# JAjchel_schemat.net
KiCad netlist of a schematic drawn in Altium Designer
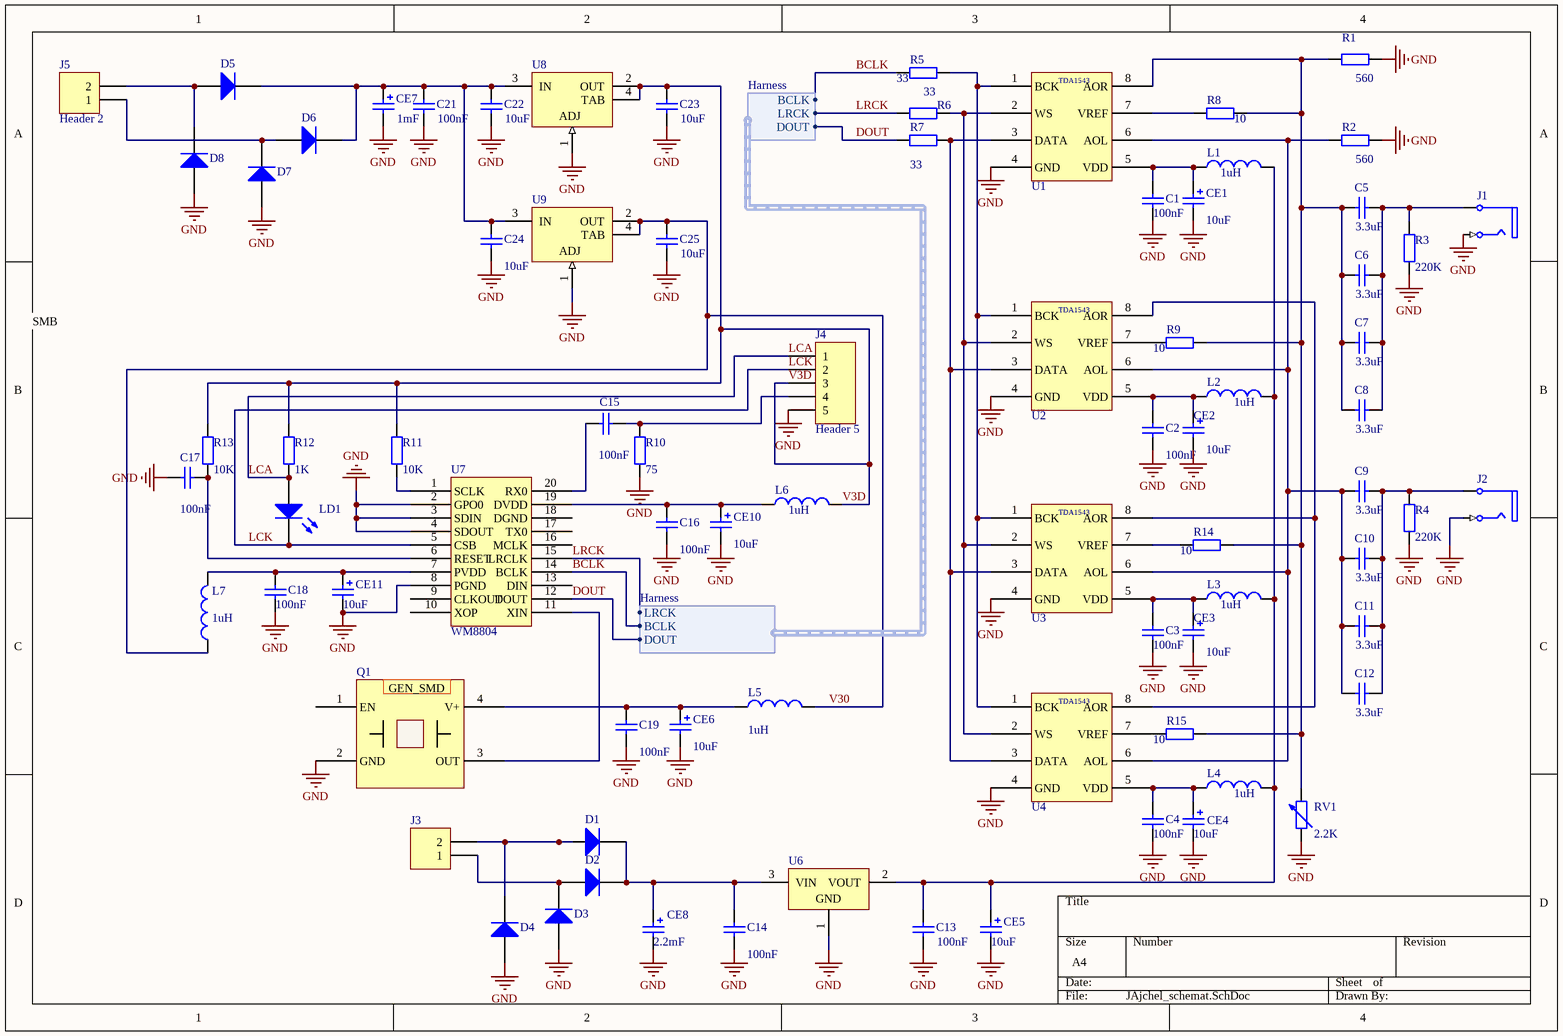
[diagram p0: JAjchel_schemat.SchDoc]

(export (version "E")
  (design (tool "Eeschema 10.0.6"))
  (components
    (comp (ref "C1")
      (value "100nF")
      (footprint "RAD-0.3")
      (description "Capacitor")
      (fields (field (name "Comment") "Cap") (field (name "PUBLISHER") "Altium Limited"))
      (libsource (lib "Miscellaneous Devices") (part "Cap"))
    )
    (comp (ref "C2")
      (value "100nF")
      (footprint "RAD-0.3")
      (description "Capacitor")
      (fields (field (name "Comment") "Cap") (field (name "PUBLISHER") "Altium Limited"))
      (libsource (lib "Miscellaneous Devices") (part "Cap"))
    )
    (comp (ref "C3")
      (value "100nF")
      (footprint "RAD-0.3")
      (description "Capacitor")
      (fields (field (name "Comment") "Cap") (field (name "PUBLISHER") "Altium Limited"))
      (libsource (lib "Miscellaneous Devices") (part "Cap"))
    )
    (comp (ref "C4")
      (value "100nF")
      (footprint "RAD-0.3")
      (description "Capacitor")
      (fields (field (name "Comment") "Cap") (field (name "PUBLISHER") "Altium Limited"))
      (libsource (lib "Miscellaneous Devices") (part "Cap"))
    )
    (comp (ref "C5")
      (value "3.3uF")
      (footprint "RAD-0.3")
      (description "Capacitor")
      (fields (field (name "Comment") "Cap") (field (name "PUBLISHER") "Altium Limited"))
      (libsource (lib "Miscellaneous Devices") (part "Cap"))
    )
    (comp (ref "C6")
      (value "3.3uF")
      (footprint "RAD-0.3")
      (description "Capacitor")
      (fields (field (name "Comment") "Cap") (field (name "PUBLISHER") "Altium Limited"))
      (libsource (lib "Miscellaneous Devices") (part "Cap"))
    )
    (comp (ref "C7")
      (value "3.3uF")
      (footprint "RAD-0.3")
      (description "Capacitor")
      (fields (field (name "Comment") "Cap") (field (name "PUBLISHER") "Altium Limited"))
      (libsource (lib "Miscellaneous Devices") (part "Cap"))
    )
    (comp (ref "C8")
      (value "3.3uF")
      (footprint "RAD-0.3")
      (description "Capacitor")
      (fields (field (name "Comment") "Cap") (field (name "PUBLISHER") "Altium Limited"))
      (libsource (lib "Miscellaneous Devices") (part "Cap"))
    )
    (comp (ref "C9")
      (value "3.3uF")
      (footprint "RAD-0.3")
      (description "Capacitor")
      (fields (field (name "Comment") "Cap") (field (name "PUBLISHER") "Altium Limited"))
      (libsource (lib "Miscellaneous Devices") (part "Cap"))
    )
    (comp (ref "C10")
      (value "3.3uF")
      (footprint "RAD-0.3")
      (description "Capacitor")
      (fields (field (name "Comment") "Cap") (field (name "PUBLISHER") "Altium Limited"))
      (libsource (lib "Miscellaneous Devices") (part "Cap"))
    )
    (comp (ref "C11")
      (value "3.3uF")
      (footprint "RAD-0.3")
      (description "Capacitor")
      (fields (field (name "Comment") "Cap") (field (name "PUBLISHER") "Altium Limited"))
      (libsource (lib "Miscellaneous Devices") (part "Cap"))
    )
    (comp (ref "C12")
      (value "3.3uF")
      (footprint "RAD-0.3")
      (description "Capacitor")
      (fields (field (name "Comment") "Cap") (field (name "PUBLISHER") "Altium Limited"))
      (libsource (lib "Miscellaneous Devices") (part "Cap"))
    )
    (comp (ref "C13")
      (value "100nF")
      (footprint "RAD-0.3")
      (description "Capacitor")
      (fields (field (name "Comment") "Cap") (field (name "PUBLISHER") "Altium Limited"))
      (libsource (lib "Miscellaneous Devices") (part "Cap"))
    )
    (comp (ref "C14")
      (value "100nF")
      (footprint "RAD-0.3")
      (description "Capacitor")
      (fields (field (name "Comment") "Cap") (field (name "PUBLISHER") "Altium Limited"))
      (libsource (lib "Miscellaneous Devices") (part "Cap"))
    )
    (comp (ref "C15")
      (value "100nF")
      (footprint "RAD-0.3")
      (description "Capacitor")
      (fields (field (name "Comment") "Cap") (field (name "PUBLISHER") "Altium Limited"))
      (libsource (lib "Miscellaneous Devices") (part "Cap"))
    )
    (comp (ref "C16")
      (value "100nF")
      (footprint "RAD-0.3")
      (description "Capacitor")
      (fields (field (name "Comment") "Cap") (field (name "PUBLISHER") "Altium Limited"))
      (libsource (lib "Miscellaneous Devices") (part "Cap"))
    )
    (comp (ref "C17")
      (value "100nF")
      (footprint "RAD-0.3")
      (description "Capacitor")
      (fields (field (name "Comment") "Cap") (field (name "PUBLISHER") "Altium Limited"))
      (libsource (lib "Miscellaneous Devices") (part "Cap"))
    )
    (comp (ref "C18")
      (value "100nF")
      (footprint "RAD-0.3")
      (description "Capacitor")
      (fields (field (name "Comment") "Cap") (field (name "PUBLISHER") "Altium Limited"))
      (libsource (lib "Miscellaneous Devices") (part "Cap"))
    )
    (comp (ref "C19")
      (value "100nF")
      (footprint "RAD-0.3")
      (description "Capacitor")
      (fields (field (name "Comment") "Cap") (field (name "PUBLISHER") "Altium Limited"))
      (libsource (lib "Miscellaneous Devices") (part "Cap"))
    )
    (comp (ref "C21")
      (value "100nF")
      (footprint "RAD-0.3")
      (description "Capacitor")
      (fields (field (name "Comment") "Cap") (field (name "PUBLISHER") "Altium Limited"))
      (libsource (lib "Miscellaneous Devices") (part "Cap"))
    )
    (comp (ref "C22")
      (value "10uF")
      (footprint "RAD-0.3")
      (description "Capacitor")
      (fields (field (name "Comment") "Cap") (field (name "PUBLISHER") "Altium Limited"))
      (libsource (lib "Miscellaneous Devices") (part "Cap"))
    )
    (comp (ref "C23")
      (value "10uF")
      (footprint "RAD-0.3")
      (description "Capacitor")
      (fields (field (name "Comment") "Cap") (field (name "PUBLISHER") "Altium Limited"))
      (libsource (lib "Miscellaneous Devices") (part "Cap"))
    )
    (comp (ref "C24")
      (value "10uF")
      (footprint "RAD-0.3")
      (description "Capacitor")
      (fields (field (name "Comment") "Cap") (field (name "PUBLISHER") "Altium Limited"))
      (libsource (lib "Miscellaneous Devices") (part "Cap"))
    )
    (comp (ref "C25")
      (value "10uF")
      (footprint "RAD-0.3")
      (description "Capacitor")
      (fields (field (name "Comment") "Cap") (field (name "PUBLISHER") "Altium Limited"))
      (libsource (lib "Miscellaneous Devices") (part "Cap"))
    )
    (comp (ref "CE1")
      (value "10uF")
      (footprint "POLAR0.8")
      (description "Polarized Capacitor (Axial)")
      (fields (field (name "Comment") "Cap Pol2") (field (name "PUBLISHER") "Altium Limited"))
      (libsource (lib "Miscellaneous Devices") (part "Cap Pol2"))
    )
    (comp (ref "CE2")
      (value "10uF")
      (footprint "POLAR0.8")
      (description "Polarized Capacitor (Axial)")
      (fields (field (name "Comment") "Cap Pol2") (field (name "PUBLISHER") "Altium Limited"))
      (libsource (lib "Miscellaneous Devices") (part "Cap Pol2"))
    )
    (comp (ref "CE3")
      (value "10uF")
      (footprint "POLAR0.8")
      (description "Polarized Capacitor (Axial)")
      (fields (field (name "Comment") "Cap Pol2") (field (name "PUBLISHER") "Altium Limited"))
      (libsource (lib "Miscellaneous Devices") (part "Cap Pol2"))
    )
    (comp (ref "CE4")
      (value "10uF")
      (footprint "POLAR0.8")
      (description "Polarized Capacitor (Axial)")
      (fields (field (name "Comment") "Cap Pol2") (field (name "PUBLISHER") "Altium Limited"))
      (libsource (lib "Miscellaneous Devices") (part "Cap Pol2"))
    )
    (comp (ref "CE5")
      (value "10uF")
      (footprint "POLAR0.8")
      (description "Polarized Capacitor (Axial)")
      (fields (field (name "Comment") "Cap Pol2") (field (name "PUBLISHER") "Altium Limited"))
      (libsource (lib "Miscellaneous Devices") (part "Cap Pol2"))
    )
    (comp (ref "CE6")
      (value "10uF")
      (footprint "POLAR0.8")
      (description "Polarized Capacitor (Axial)")
      (fields (field (name "Comment") "Cap Pol2") (field (name "PUBLISHER") "Altium Limited"))
      (libsource (lib "Miscellaneous Devices") (part "Cap Pol2"))
    )
    (comp (ref "CE7")
      (value "1mF")
      (footprint "POLAR0.8")
      (description "Polarized Capacitor (Axial)")
      (fields (field (name "Comment") "Cap Pol2") (field (name "PUBLISHER") "Altium Limited"))
      (libsource (lib "Miscellaneous Devices") (part "Cap Pol2"))
    )
    (comp (ref "CE8")
      (value "2.2mF")
      (footprint "POLAR0.8")
      (description "Polarized Capacitor (Axial)")
      (fields (field (name "Comment") "Cap Pol2") (field (name "PUBLISHER") "Altium Limited"))
      (libsource (lib "Miscellaneous Devices") (part "Cap Pol2"))
    )
    (comp (ref "CE10")
      (value "10uF")
      (footprint "POLAR0.8")
      (description "Polarized Capacitor (Axial)")
      (fields (field (name "Comment") "Cap Pol2") (field (name "PUBLISHER") "Altium Limited"))
      (libsource (lib "Miscellaneous Devices") (part "Cap Pol2"))
    )
    (comp (ref "CE11")
      (value "10uF")
      (footprint "POLAR0.8")
      (description "Polarized Capacitor (Axial)")
      (fields (field (name "Comment") "Cap Pol2") (field (name "PUBLISHER") "Altium Limited"))
      (libsource (lib "Miscellaneous Devices") (part "Cap Pol2"))
    )
    (comp (ref "D1") (value "D-AK-2") (libsource (lib "D-AK-2") (part "D-AK-2")))
    (comp (ref "D2") (value "D-AK-2") (libsource (lib "D-AK-2") (part "D-AK-2")))
    (comp (ref "D3") (value "D-AK-2") (libsource (lib "D-AK-2") (part "D-AK-2")))
    (comp (ref "D4") (value "D-AK-2") (libsource (lib "Altium Content Vault") (part "SYM-0080-00036-1")))
    (comp (ref "D5") (value "D-AK-2") (libsource (lib "D-AK-2") (part "D-AK-2")))
    (comp (ref "D6") (value "D-AK-2") (libsource (lib "D-AK-2") (part "D-AK-2")))
    (comp (ref "D7") (value "D-AK-2") (libsource (lib "D-AK-2") (part "D-AK-2")))
    (comp (ref "D8") (value "D-AK-2") (libsource (lib "D-AK-2") (part "D-AK-2")))
    (comp (ref "J1")
      (value "RCA")
      (footprint "RCA/4.5-H2")
      (description "RCA Phono Jack, Right Angle, Thru-Hole, Snap-In")
      (fields (field (name "PUBLISHER") "Altium Limited"))
      (libsource (lib "Miscellaneous Connectors") (part "RCA"))
    )
    (comp (ref "J2")
      (value "RCA")
      (footprint "RCA/4.5-H2")
      (description "RCA Phono Jack, Right Angle, Thru-Hole, Snap-In")
      (fields (field (name "PUBLISHER") "Altium Limited"))
      (libsource (lib "Miscellaneous Connectors") (part "RCA"))
    )
    (comp (ref "J3")
      (value "Header 2")
      (footprint "HDR1X2")
      (description "Header, 2-Pin")
      (fields (field (name "PUBLISHER") "Altium Limited"))
      (libsource (lib "Miscellaneous Connectors") (part "Header 2"))
    )
    (comp (ref "J4")
      (value "Header 5")
      (footprint "HDR1X5")
      (description "Header, 5-Pin")
      (fields (field (name "PUBLISHER") "Altium Limited"))
      (libsource (lib "Miscellaneous Connectors") (part "Header 5"))
    )
    (comp (ref "J5")
      (value "Header 2")
      (footprint "HDR1X2")
      (description "Header, 2-Pin")
      (fields (field (name "PUBLISHER") "Altium Limited"))
      (libsource (lib "Miscellaneous Connectors") (part "Header 2"))
    )
    (comp (ref "L1")
      (value "1uH")
      (footprint "0402-A")
      (description "Inductor")
      (fields (field (name "PUBLISHER") "Altium Limited"))
      (libsource (lib "Miscellaneous Devices") (part "Inductor"))
    )
    (comp (ref "L2")
      (value "1uH")
      (footprint "0402-A")
      (description "Inductor")
      (fields (field (name "PUBLISHER") "Altium Limited"))
      (libsource (lib "Miscellaneous Devices") (part "Inductor"))
    )
    (comp (ref "L3")
      (value "1uH")
      (footprint "0402-A")
      (description "Inductor")
      (fields (field (name "PUBLISHER") "Altium Limited"))
      (libsource (lib "Miscellaneous Devices") (part "Inductor"))
    )
    (comp (ref "L4")
      (value "1uH")
      (footprint "0402-A")
      (description "Inductor")
      (fields (field (name "PUBLISHER") "Altium Limited"))
      (libsource (lib "Miscellaneous Devices") (part "Inductor"))
    )
    (comp (ref "L5")
      (value "1uH")
      (footprint "0402-A")
      (description "Inductor")
      (fields (field (name "PUBLISHER") "Altium Limited"))
      (libsource (lib "Miscellaneous Devices") (part "Inductor"))
    )
    (comp (ref "L6")
      (value "1uH")
      (footprint "0402-A")
      (description "Inductor")
      (fields (field (name "PUBLISHER") "Altium Limited"))
      (libsource (lib "Miscellaneous Devices") (part "Inductor"))
    )
    (comp (ref "L7")
      (value "1uH")
      (footprint "0402-A")
      (description "Inductor")
      (fields (field (name "PUBLISHER") "Altium Limited"))
      (libsource (lib "Miscellaneous Devices") (part "Inductor"))
    )
    (comp (ref "LD1")
      (value "LED1")
      (footprint "LED-1")
      (description "Typical RED GaAs LED")
      (fields (field (name "PUBLISHER") "Altium Limited"))
      (libsource (lib "Miscellaneous Devices") (part "LED1"))
    )
    (comp (ref "Q1")
      (value "12MHz")
      (description "Oscilator 12MHz")
      (libsource (lib "JAjchel_projekt") (part "Oscilator12mhz"))
    )
    (comp (ref "R1")
      (value "560")
      (footprint "AXIAL-0.4")
      (description "Resistor")
      (fields (field (name "Comment") "Res2") (field (name "PUBLISHER") "Altium Limited"))
      (libsource (lib "Miscellaneous Devices") (part "Res2"))
    )
    (comp (ref "R2")
      (value "560")
      (footprint "AXIAL-0.4")
      (description "Resistor")
      (fields (field (name "Comment") "Res2") (field (name "PUBLISHER") "Altium Limited"))
      (libsource (lib "Miscellaneous Devices") (part "Res2"))
    )
    (comp (ref "R3")
      (value "220K")
      (footprint "AXIAL-0.4")
      (description "Resistor")
      (fields (field (name "Comment") "Res2") (field (name "PUBLISHER") "Altium Limited"))
      (libsource (lib "") (part "Res2_1"))
    )
    (comp (ref "R4")
      (value "220K")
      (footprint "AXIAL-0.4")
      (description "Resistor")
      (fields (field (name "Comment") "Res2") (field (name "PUBLISHER") "Altium Limited"))
      (libsource (lib "") (part "Res2_1"))
    )
    (comp (ref "R5")
      (value "33")
      (footprint "AXIAL-0.4")
      (description "Resistor")
      (fields (field (name "Comment") "Res2") (field (name "PUBLISHER") "Altium Limited"))
      (libsource (lib "Miscellaneous Devices") (part "Res2"))
    )
    (comp (ref "R6")
      (value "33")
      (footprint "AXIAL-0.4")
      (description "Resistor")
      (fields (field (name "Comment") "Res2") (field (name "PUBLISHER") "Altium Limited"))
      (libsource (lib "Miscellaneous Devices") (part "Res2"))
    )
    (comp (ref "R7")
      (value "33")
      (footprint "AXIAL-0.4")
      (description "Resistor")
      (fields (field (name "Comment") "Res2") (field (name "PUBLISHER") "Altium Limited"))
      (libsource (lib "Miscellaneous Devices") (part "Res2"))
    )
    (comp (ref "R8")
      (value "10")
      (footprint "AXIAL-0.4")
      (description "Resistor")
      (fields (field (name "Comment") "Res2") (field (name "PUBLISHER") "Altium Limited"))
      (libsource (lib "Miscellaneous Devices") (part "Res2"))
    )
    (comp (ref "R9")
      (value "10")
      (footprint "AXIAL-0.4")
      (description "Resistor")
      (fields (field (name "Comment") "Res2") (field (name "PUBLISHER") "Altium Limited"))
      (libsource (lib "Miscellaneous Devices") (part "Res2"))
    )
    (comp (ref "R10")
      (value "75")
      (footprint "AXIAL-0.4")
      (description "Resistor")
      (fields (field (name "Comment") "Res2") (field (name "PUBLISHER") "Altium Limited"))
      (libsource (lib "") (part "Res2_1"))
    )
    (comp (ref "R11")
      (value "10K")
      (footprint "AXIAL-0.4")
      (description "Resistor")
      (fields (field (name "Comment") "Res2") (field (name "PUBLISHER") "Altium Limited"))
      (libsource (lib "") (part "Res2_1"))
    )
    (comp (ref "R12")
      (value "1K")
      (footprint "AXIAL-0.4")
      (description "Resistor")
      (fields (field (name "Comment") "Res2") (field (name "PUBLISHER") "Altium Limited"))
      (libsource (lib "") (part "Res2_1"))
    )
    (comp (ref "R13")
      (value "10K")
      (footprint "AXIAL-0.4")
      (description "Resistor")
      (fields (field (name "Comment") "Res2") (field (name "PUBLISHER") "Altium Limited"))
      (libsource (lib "") (part "Res2_1"))
    )
    (comp (ref "R14")
      (value "10")
      (footprint "AXIAL-0.4")
      (description "Resistor")
      (fields (field (name "Comment") "Res2") (field (name "PUBLISHER") "Altium Limited"))
      (libsource (lib "Miscellaneous Devices") (part "Res2"))
    )
    (comp (ref "R15")
      (value "10")
      (footprint "AXIAL-0.4")
      (description "Resistor")
      (fields (field (name "Comment") "Res2") (field (name "PUBLISHER") "Altium Limited"))
      (libsource (lib "Miscellaneous Devices") (part "Res2"))
    )
    (comp (ref "RV1")
      (value "2.2K")
      (footprint "AXIAL-0.6")
      (description "Variable Resistor")
      (fields (field (name "Comment") "Res Adj2") (field (name "PUBLISHER") "Altium Limited"))
      (libsource (lib "Miscellaneous Devices") (part "Res Adj2"))
    )
    (comp (ref "U1") (value "TDA1543") (libsource (lib "TDA1543") (part "TDA1543")))
    (comp (ref "U2") (value "TDA1543") (libsource (lib "TDA1543") (part "TDA1543")))
    (comp (ref "U3") (value "TDA1543") (libsource (lib "TDA1543") (part "TDA1543")))
    (comp (ref "U4") (value "TDA1543") (libsource (lib "TDA1543") (part "TDA1543")))
    (comp (ref "U6") (value "LT-LT1086-T-3") (libsource (lib "LT-LT1086-T-3") (part "LT-LT1086-T-3")))
    (comp (ref "U7") (value "WM8804") (libsource (lib "TDA1543") (part "WM8804")))
    (comp (ref "U8")
      (value "PM-REG-LM1086ADJ-SOT4")
      (libsource (lib "PM-REG-LM1086ADJ-SOT4") (part "PM-REG-LM1086ADJ-SOT4"))
    )
    (comp (ref "U9")
      (value "PM-REG-LM1086ADJ-SOT4")
      (libsource (lib "PM-REG-LM1086ADJ-SOT4") (part "PM-REG-LM1086ADJ-SOT4"))
    )
  )
  (nets
    (net (code "2") (name "/BCLK") (class "Default")
      (node (ref "R5") (pin "1") (pinfunction "1_1") (pintype "passive"))
      (node (ref "U7") (pin "14") (pinfunction "BCLK_14") (pintype "passive"))
    )
    (net (code "3") (name "/DOUT") (class "Default")
      (node (ref "R7") (pin "1") (pinfunction "1_1") (pintype "passive"))
      (node (ref "U7") (pin "12") (pinfunction "DOUT_12") (pintype "passive"))
    )
    (net (code "4") (name "/LCA") (class "Default")
      (node (ref "J4") (pin "1") (pinfunction "1_1") (pintype "passive"))
      (node (ref "LD1") (pin "1") (pinfunction "A_1") (pintype "passive"))
      (node (ref "R12") (pin "1") (pinfunction "1_1") (pintype "passive"))
    )
    (net (code "5") (name "/LCK") (class "Default")
      (node (ref "J4") (pin "2") (pinfunction "2_2") (pintype "passive"))
      (node (ref "LD1") (pin "2") (pinfunction "K_2") (pintype "passive"))
      (node (ref "U7") (pin "5") (pinfunction "CSB_5") (pintype "passive"))
    )
    (net (code "6") (name "/LRCK") (class "Default")
      (node (ref "R6") (pin "1") (pinfunction "1_1") (pintype "passive"))
      (node (ref "U7") (pin "15") (pinfunction "LRCLK_15") (pintype "passive"))
    )
    (net (code "7") (name "/V3D") (class "Default")
      (node (ref "C23") (pin "2") (pinfunction "2_2") (pintype "passive"))
      (node (ref "J4") (pin "3") (pinfunction "3_3") (pintype "passive"))
      (node (ref "L6") (pin "2") (pinfunction "2_2") (pintype "passive"))
      (node (ref "R11") (pin "2") (pinfunction "2_2") (pintype "passive"))
      (node (ref "R12") (pin "2") (pinfunction "2_2") (pintype "passive"))
      (node (ref "R13") (pin "2") (pinfunction "2_2") (pintype "passive"))
      (node (ref "U8") (pin "2") (pinfunction "OUT_2") (pintype "power_in"))
      (node (ref "U8") (pin "4") (pinfunction "TAB_4") (pintype "power_in"))
    )
    (net (code "8") (name "/V30") (class "Default")
      (node (ref "C25") (pin "2") (pinfunction "2_2") (pintype "passive"))
      (node (ref "L5") (pin "2") (pinfunction "2_2") (pintype "passive"))
      (node (ref "L7") (pin "1") (pinfunction "1_1") (pintype "passive"))
      (node (ref "U9") (pin "2") (pinfunction "OUT_2") (pintype "power_in"))
      (node (ref "U9") (pin "4") (pinfunction "TAB_4") (pintype "power_in"))
    )
    (net (code "10") (name "GND") (class "Default")
      (node (ref "C1") (pin "1") (pinfunction "1_1") (pintype "passive"))
      (node (ref "C13") (pin "1") (pinfunction "1_1") (pintype "passive"))
      (node (ref "C14") (pin "1") (pinfunction "1_1") (pintype "passive"))
      (node (ref "C16") (pin "1") (pinfunction "1_1") (pintype "passive"))
      (node (ref "C17") (pin "1") (pinfunction "1_1") (pintype "passive"))
      (node (ref "C18") (pin "1") (pinfunction "1_1") (pintype "passive"))
      (node (ref "C19") (pin "1") (pinfunction "1_1") (pintype "passive"))
      (node (ref "C2") (pin "1") (pinfunction "1_1") (pintype "passive"))
      (node (ref "C21") (pin "1") (pinfunction "1_1") (pintype "passive"))
      (node (ref "C22") (pin "1") (pinfunction "1_1") (pintype "passive"))
      (node (ref "C23") (pin "1") (pinfunction "1_1") (pintype "passive"))
      (node (ref "C24") (pin "1") (pinfunction "1_1") (pintype "passive"))
      (node (ref "C25") (pin "1") (pinfunction "1_1") (pintype "passive"))
      (node (ref "C3") (pin "1") (pinfunction "1_1") (pintype "passive"))
      (node (ref "C4") (pin "1") (pinfunction "1_1") (pintype "passive"))
      (node (ref "CE1") (pin "2") (pinfunction "2_2") (pintype "passive"))
      (node (ref "CE10") (pin "2") (pinfunction "2_2") (pintype "passive"))
      (node (ref "CE11") (pin "2") (pinfunction "2_2") (pintype "passive"))
      (node (ref "CE2") (pin "2") (pinfunction "2_2") (pintype "passive"))
      (node (ref "CE3") (pin "2") (pinfunction "2_2") (pintype "passive"))
      (node (ref "CE4") (pin "2") (pinfunction "2_2") (pintype "passive"))
      (node (ref "CE5") (pin "2") (pinfunction "2_2") (pintype "passive"))
      (node (ref "CE6") (pin "2") (pinfunction "2_2") (pintype "passive"))
      (node (ref "CE7") (pin "2") (pinfunction "2_2") (pintype "passive"))
      (node (ref "CE8") (pin "2") (pinfunction "2_2") (pintype "passive"))
      (node (ref "D3") (pin "1") (pinfunction "A_1") (pintype "passive"))
      (node (ref "D4") (pin "1") (pinfunction "A_1") (pintype "passive"))
      (node (ref "D7") (pin "1") (pinfunction "A_1") (pintype "passive"))
      (node (ref "D8") (pin "1") (pinfunction "A_1") (pintype "passive"))
      (node (ref "J1") (pin "2B") (pinfunction "Signal_2B") (pintype "input"))
      (node (ref "J2") (pin "2B") (pinfunction "Signal_2B") (pintype "input"))
      (node (ref "J4") (pin "5") (pinfunction "5_5") (pintype "passive"))
      (node (ref "Q1") (pin "2") (pinfunction "GND_2") (pintype "passive"))
      (node (ref "R1") (pin "2") (pinfunction "2_2") (pintype "passive"))
      (node (ref "R10") (pin "1") (pinfunction "1_1") (pintype "passive"))
      (node (ref "R2") (pin "2") (pinfunction "2_2") (pintype "passive"))
      (node (ref "R3") (pin "1") (pinfunction "1_1") (pintype "passive"))
      (node (ref "R4") (pin "1") (pinfunction "1_1") (pintype "passive"))
      (node (ref "RV1") (pin "1") (pinfunction "1_1") (pintype "passive"))
      (node (ref "U1") (pin "4") (pinfunction "GND_4") (pintype "passive"))
      (node (ref "U2") (pin "4") (pinfunction "GND_4") (pintype "passive"))
      (node (ref "U3") (pin "4") (pinfunction "GND_4") (pintype "passive"))
      (node (ref "U4") (pin "4") (pinfunction "GND_4") (pintype "passive"))
      (node (ref "U6") (pin "1") (pinfunction "GND_1") (pintype "power_in"))
      (node (ref "U7") (pin "2") (pinfunction "GPO0_2") (pintype "passive"))
      (node (ref "U7") (pin "3") (pinfunction "SDIN_3") (pintype "passive"))
      (node (ref "U7") (pin "4") (pinfunction "SDOUT_4") (pintype "passive"))
      (node (ref "U7") (pin "8") (pinfunction "PGND_8") (pintype "passive"))
      (node (ref "U8") (pin "1") (pinfunction "ADJ_1") (pintype "input"))
      (node (ref "U9") (pin "1") (pinfunction "ADJ_1") (pintype "input"))
    )
    (net (code "11") (name "Net-(C15-Pad2)") (class "Default")
      (node (ref "C15") (pin "2") (pinfunction "2_2") (pintype "passive"))
      (node (ref "J4") (pin "4") (pinfunction "4_4") (pintype "passive"))
      (node (ref "R10") (pin "2") (pinfunction "2_2") (pintype "passive"))
    )
    (net (code "12") (name "Net-(D1-A)") (class "Default")
      (node (ref "D1") (pin "1") (pinfunction "A_1") (pintype "passive"))
      (node (ref "D4") (pin "2") (pinfunction "K_2") (pintype "passive"))
      (node (ref "J3") (pin "2") (pinfunction "2_2") (pintype "passive"))
    )
    (net (code "13") (name "Net-(D1-K)") (class "Default")
      (node (ref "C14") (pin "2") (pinfunction "2_2") (pintype "passive"))
      (node (ref "CE8") (pin "1") (pinfunction "1_1") (pintype "passive"))
      (node (ref "D1") (pin "2") (pinfunction "K_2") (pintype "passive"))
      (node (ref "D2") (pin "2") (pinfunction "K_2") (pintype "passive"))
      (node (ref "U6") (pin "3") (pinfunction "VIN_3") (pintype "power_in"))
    )
    (net (code "14") (name "Net-(D2-A)") (class "Default")
      (node (ref "D2") (pin "1") (pinfunction "A_1") (pintype "passive"))
      (node (ref "D3") (pin "2") (pinfunction "K_2") (pintype "passive"))
      (node (ref "J3") (pin "1") (pinfunction "1_1") (pintype "passive"))
    )
    (net (code "15") (name "Net-(D5-A)") (class "Default")
      (node (ref "D5") (pin "1") (pinfunction "A_1") (pintype "passive"))
      (node (ref "D8") (pin "2") (pinfunction "K_2") (pintype "passive"))
      (node (ref "J5") (pin "2") (pinfunction "2_2") (pintype "passive"))
    )
    (net (code "16") (name "Net-(D5-K)") (class "Default")
      (node (ref "C21") (pin "2") (pinfunction "2_2") (pintype "passive"))
      (node (ref "C22") (pin "2") (pinfunction "2_2") (pintype "passive"))
      (node (ref "C24") (pin "2") (pinfunction "2_2") (pintype "passive"))
      (node (ref "CE7") (pin "1") (pinfunction "1_1") (pintype "passive"))
      (node (ref "D5") (pin "2") (pinfunction "K_2") (pintype "passive"))
      (node (ref "D6") (pin "2") (pinfunction "K_2") (pintype "passive"))
      (node (ref "U8") (pin "3") (pinfunction "IN_3") (pintype "power_in"))
      (node (ref "U9") (pin "3") (pinfunction "IN_3") (pintype "power_in"))
    )
    (net (code "17") (name "Net-(D6-A)") (class "Default")
      (node (ref "D6") (pin "1") (pinfunction "A_1") (pintype "passive"))
      (node (ref "D7") (pin "2") (pinfunction "K_2") (pintype "passive"))
      (node (ref "J5") (pin "1") (pinfunction "1_1") (pintype "passive"))
    )
    (net (code "18") (name "Net-(J1-Ground)") (class "Default")
      (node (ref "C5") (pin "2") (pinfunction "2_2") (pintype "passive"))
      (node (ref "C6") (pin "2") (pinfunction "2_2") (pintype "passive"))
      (node (ref "C7") (pin "2") (pinfunction "2_2") (pintype "passive"))
      (node (ref "C8") (pin "2") (pinfunction "2_2") (pintype "passive"))
      (node (ref "J1") (pin "1A") (pinfunction "Ground_1A") (pintype "power_in"))
      (node (ref "R3") (pin "2") (pinfunction "2_2") (pintype "passive"))
    )
    (net (code "19") (name "Net-(J2-Ground)") (class "Default")
      (node (ref "C10") (pin "2") (pinfunction "2_2") (pintype "passive"))
      (node (ref "C11") (pin "2") (pinfunction "2_2") (pintype "passive"))
      (node (ref "C12") (pin "2") (pinfunction "2_2") (pintype "passive"))
      (node (ref "C9") (pin "2") (pinfunction "2_2") (pintype "passive"))
      (node (ref "J2") (pin "1A") (pinfunction "Ground_1A") (pintype "power_in"))
      (node (ref "R4") (pin "2") (pinfunction "2_2") (pintype "passive"))
    )
    (net (code "20") (name "Net-(Q1-OUT)") (class "Default")
      (node (ref "Q1") (pin "3") (pinfunction "OUT_3") (pintype "passive"))
      (node (ref "U7") (pin "11") (pinfunction "XIN_11") (pintype "passive"))
    )
    (net (code "21") (name "Net-(Q1-V+)") (class "Default")
      (node (ref "C19") (pin "2") (pinfunction "2_2") (pintype "passive"))
      (node (ref "CE6") (pin "1") (pinfunction "1_1") (pintype "passive"))
      (node (ref "L5") (pin "1") (pinfunction "1_1") (pintype "passive"))
      (node (ref "Q1") (pin "4") (pinfunction "V+_4") (pintype "passive"))
    )
    (net (code "22") (name "Net-(U1-AOL)") (class "Default")
      (node (ref "C10") (pin "1") (pinfunction "1_1") (pintype "passive"))
      (node (ref "C11") (pin "1") (pinfunction "1_1") (pintype "passive"))
      (node (ref "C12") (pin "1") (pinfunction "1_1") (pintype "passive"))
      (node (ref "C9") (pin "1") (pinfunction "1_1") (pintype "passive"))
      (node (ref "R2") (pin "1") (pinfunction "1_1") (pintype "passive"))
      (node (ref "U1") (pin "6") (pinfunction "AOL_6") (pintype "passive"))
      (node (ref "U2") (pin "6") (pinfunction "AOL_6") (pintype "passive"))
      (node (ref "U3") (pin "6") (pinfunction "AOL_6") (pintype "passive"))
      (node (ref "U4") (pin "6") (pinfunction "AOL_6") (pintype "passive"))
    )
    (net (code "23") (name "Net-(U1-AOR)") (class "Default")
      (node (ref "C5") (pin "1") (pinfunction "1_1") (pintype "passive"))
      (node (ref "C6") (pin "1") (pinfunction "1_1") (pintype "passive"))
      (node (ref "C7") (pin "1") (pinfunction "1_1") (pintype "passive"))
      (node (ref "C8") (pin "1") (pinfunction "1_1") (pintype "passive"))
      (node (ref "R1") (pin "1") (pinfunction "1_1") (pintype "passive"))
      (node (ref "R14") (pin "2") (pinfunction "2_2") (pintype "passive"))
      (node (ref "R15") (pin "2") (pinfunction "2_2") (pintype "passive"))
      (node (ref "R8") (pin "2") (pinfunction "2_2") (pintype "passive"))
      (node (ref "R9") (pin "2") (pinfunction "2_2") (pintype "passive"))
      (node (ref "RV1") (pin "2") (pinfunction "2_2") (pintype "passive"))
      (node (ref "U1") (pin "8") (pinfunction "AOR_8") (pintype "passive"))
    )
    (net (code "24") (name "Net-(U1-BCK)") (class "Default")
      (node (ref "R5") (pin "2") (pinfunction "2_2") (pintype "passive"))
      (node (ref "U1") (pin "1") (pinfunction "BCK_1") (pintype "passive"))
      (node (ref "U2") (pin "1") (pinfunction "BCK_1") (pintype "passive"))
      (node (ref "U3") (pin "1") (pinfunction "BCK_1") (pintype "passive"))
      (node (ref "U4") (pin "1") (pinfunction "BCK_1") (pintype "passive"))
    )
    (net (code "25") (name "Net-(U1-DATA)") (class "Default")
      (node (ref "R7") (pin "2") (pinfunction "2_2") (pintype "passive"))
      (node (ref "U1") (pin "3") (pinfunction "DATA_3") (pintype "passive"))
      (node (ref "U2") (pin "3") (pinfunction "DATA_3") (pintype "passive"))
      (node (ref "U3") (pin "3") (pinfunction "DATA_3") (pintype "passive"))
      (node (ref "U4") (pin "3") (pinfunction "DATA_3") (pintype "passive"))
    )
    (net (code "26") (name "Net-(U1-VDD)") (class "Default")
      (node (ref "C1") (pin "2") (pinfunction "2_2") (pintype "passive"))
      (node (ref "CE1") (pin "1") (pinfunction "1_1") (pintype "passive"))
      (node (ref "L1") (pin "1") (pinfunction "1_1") (pintype "passive"))
      (node (ref "U1") (pin "5") (pinfunction "VDD_5") (pintype "passive"))
    )
    (net (code "27") (name "Net-(U1-VREF)") (class "Default")
      (node (ref "R8") (pin "1") (pinfunction "1_1") (pintype "passive"))
      (node (ref "U1") (pin "7") (pinfunction "VREF_7") (pintype "passive"))
    )
    (net (code "28") (name "Net-(U1-WS)") (class "Default")
      (node (ref "R6") (pin "2") (pinfunction "2_2") (pintype "passive"))
      (node (ref "U1") (pin "2") (pinfunction "WS_2") (pintype "passive"))
      (node (ref "U2") (pin "2") (pinfunction "WS_2") (pintype "passive"))
      (node (ref "U3") (pin "2") (pinfunction "WS_2") (pintype "passive"))
      (node (ref "U4") (pin "2") (pinfunction "WS_2") (pintype "passive"))
    )
    (net (code "29") (name "Net-(U2-AOR)") (class "Default")
      (node (ref "U2") (pin "8") (pinfunction "AOR_8") (pintype "passive"))
      (node (ref "U3") (pin "8") (pinfunction "AOR_8") (pintype "passive"))
      (node (ref "U4") (pin "8") (pinfunction "AOR_8") (pintype "passive"))
    )
    (net (code "30") (name "Net-(U2-VDD)") (class "Default")
      (node (ref "C2") (pin "2") (pinfunction "2_2") (pintype "passive"))
      (node (ref "CE2") (pin "1") (pinfunction "1_1") (pintype "passive"))
      (node (ref "L2") (pin "1") (pinfunction "1_1") (pintype "passive"))
      (node (ref "U2") (pin "5") (pinfunction "VDD_5") (pintype "passive"))
    )
    (net (code "31") (name "Net-(U2-VREF)") (class "Default")
      (node (ref "R9") (pin "1") (pinfunction "1_1") (pintype "passive"))
      (node (ref "U2") (pin "7") (pinfunction "VREF_7") (pintype "passive"))
    )
    (net (code "32") (name "Net-(U3-VDD)") (class "Default")
      (node (ref "C3") (pin "2") (pinfunction "2_2") (pintype "passive"))
      (node (ref "CE3") (pin "1") (pinfunction "1_1") (pintype "passive"))
      (node (ref "L3") (pin "1") (pinfunction "1_1") (pintype "passive"))
      (node (ref "U3") (pin "5") (pinfunction "VDD_5") (pintype "passive"))
    )
    (net (code "33") (name "Net-(U3-VREF)") (class "Default")
      (node (ref "R14") (pin "1") (pinfunction "1_1") (pintype "passive"))
      (node (ref "U3") (pin "7") (pinfunction "VREF_7") (pintype "passive"))
    )
    (net (code "34") (name "Net-(U4-VDD)") (class "Default")
      (node (ref "C4") (pin "2") (pinfunction "2_2") (pintype "passive"))
      (node (ref "CE4") (pin "1") (pinfunction "1_1") (pintype "passive"))
      (node (ref "L4") (pin "1") (pinfunction "1_1") (pintype "passive"))
      (node (ref "U4") (pin "5") (pinfunction "VDD_5") (pintype "passive"))
    )
    (net (code "35") (name "Net-(U4-VREF)") (class "Default")
      (node (ref "R15") (pin "1") (pinfunction "1_1") (pintype "passive"))
      (node (ref "U4") (pin "7") (pinfunction "VREF_7") (pintype "passive"))
    )
    (net (code "36") (name "Net-(U6-VOUT)") (class "Default")
      (node (ref "C13") (pin "2") (pinfunction "2_2") (pintype "passive"))
      (node (ref "CE5") (pin "1") (pinfunction "1_1") (pintype "passive"))
      (node (ref "L1") (pin "2") (pinfunction "2_2") (pintype "passive"))
      (node (ref "L2") (pin "2") (pinfunction "2_2") (pintype "passive"))
      (node (ref "L3") (pin "2") (pinfunction "2_2") (pintype "passive"))
      (node (ref "L4") (pin "2") (pinfunction "2_2") (pintype "passive"))
      (node (ref "U6") (pin "2") (pinfunction "VOUT_2") (pintype "power_in"))
    )
    (net (code "37") (name "Net-(U7-DVDD)") (class "Default")
      (node (ref "C16") (pin "2") (pinfunction "2_2") (pintype "passive"))
      (node (ref "CE10") (pin "1") (pinfunction "1_1") (pintype "passive"))
      (node (ref "L6") (pin "1") (pinfunction "1_1") (pintype "passive"))
      (node (ref "U7") (pin "19") (pinfunction "DVDD_19") (pintype "passive"))
    )
    (net (code "38") (name "Net-(U7-PVDD)") (class "Default")
      (node (ref "C18") (pin "2") (pinfunction "2_2") (pintype "passive"))
      (node (ref "CE11") (pin "1") (pinfunction "1_1") (pintype "passive"))
      (node (ref "L7") (pin "2") (pinfunction "2_2") (pintype "passive"))
      (node (ref "U7") (pin "7") (pinfunction "PVDD_7") (pintype "passive"))
    )
    (net (code "39") (name "Net-(U7-RESET)") (class "Default")
      (node (ref "C17") (pin "2") (pinfunction "2_2") (pintype "passive"))
      (node (ref "R13") (pin "1") (pinfunction "1_1") (pintype "passive"))
      (node (ref "U7") (pin "6") (pinfunction "RESET_6") (pintype "passive"))
    )
    (net (code "40") (name "Net-(U7-RX0)") (class "Default")
      (node (ref "C15") (pin "1") (pinfunction "1_1") (pintype "passive"))
      (node (ref "U7") (pin "20") (pinfunction "RX0_20") (pintype "passive"))
    )
    (net (code "41") (name "Net-(U7-SCLK)") (class "Default")
      (node (ref "R11") (pin "1") (pinfunction "1_1") (pintype "passive"))
      (node (ref "U7") (pin "1") (pinfunction "SCLK_1") (pintype "passive"))
    )
    (net (code "42") (name "unconnected-(Q1-EN-Pad1)") (class "Default")
      (node (ref "Q1") (pin "1") (pinfunction "EN_1") (pintype "passive"))
    )
    (net (code "43") (name "unconnected-(U7-CLKOUT-Pad9)") (class "Default")
      (node (ref "U7") (pin "9") (pinfunction "CLKOUT_9") (pintype "passive"))
    )
    (net (code "44") (name "unconnected-(U7-DGND-Pad18)") (class "Default")
      (node (ref "U7") (pin "18") (pinfunction "DGND_18") (pintype "passive"))
    )
    (net (code "45") (name "unconnected-(U7-DIN-Pad13)") (class "Default")
      (node (ref "U7") (pin "13") (pinfunction "DIN_13") (pintype "passive"))
    )
    (net (code "46") (name "unconnected-(U7-MCLK-Pad16)") (class "Default")
      (node (ref "U7") (pin "16") (pinfunction "MCLK_16") (pintype "passive"))
    )
    (net (code "47") (name "unconnected-(U7-TX0-Pad17)") (class "Default")
      (node (ref "U7") (pin "17") (pinfunction "TX0_17") (pintype "passive"))
    )
    (net (code "48") (name "unconnected-(U7-XOP-Pad10)") (class "Default")
      (node (ref "U7") (pin "10") (pinfunction "XOP_10") (pintype "passive"))
    )
  )
)
